# Raspberry.net
KiCad netlist of a schematic drawn in Altium Designer
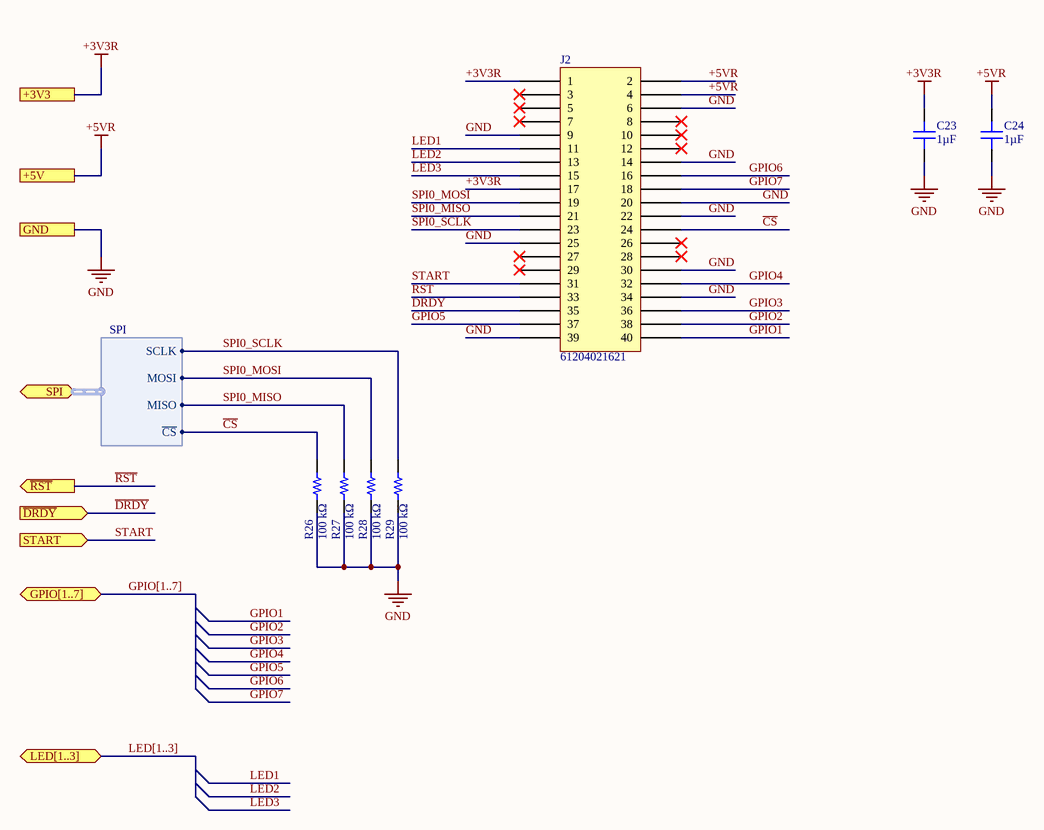
[diagram p0: Raspberry.SchDoc]

(export (version "E")
  (design (tool "Eeschema 10.0.6"))
  (components
    (comp (ref "C23")
      (value "1µF")
      (footprint "CAP 0402_1005")
      (description "CAP CER 1UF 16V X5R 0402")
      (fields (field (name "PART NUMBER") "0402BW105K160NGT") (field (name "MANUFACTURER") "Knowles Novacap"))
      (libsource (lib "Generic Altium Database") (part "Capacitor"))
    )
    (comp (ref "C24")
      (value "1µF")
      (footprint "CAP 0402_1005")
      (description "CAP CER 1UF 16V X5R 0402")
      (fields (field (name "PART NUMBER") "0402BW105K160NGT") (field (name "MANUFACTURER") "Knowles Novacap"))
      (libsource (lib "Generic Altium Database") (part "Capacitor"))
    )
    (comp (ref "J2")
      (value "61204021621")
      (footprint "WURTH 61204021621")
      (description "CONN HEADER VERT 40POS 2.54MM")
      (fields (field (name "MANUFACTURER") "Würth Elektronik"))
      (libsource (lib "Generic Altium Database") (part "2X20 PIN"))
    )
    (comp (ref "R26")
      (value "100 kΩ")
      (footprint "RES 0402_1005")
      (description "RES SMD 100K OHM 1% 1/16W 0402")
      (fields (field (name "PART NUMBER") "AC0402FR-07100KL") (field (name "MANUFACTURER") "Yageo"))
      (libsource (lib "Generic Altium Database") (part "Resistor"))
    )
    (comp (ref "R27")
      (value "100 kΩ")
      (footprint "RES 0402_1005")
      (description "RES SMD 100K OHM 1% 1/16W 0402")
      (fields (field (name "PART NUMBER") "AC0402FR-07100KL") (field (name "MANUFACTURER") "Yageo"))
      (libsource (lib "Generic Altium Database") (part "Resistor"))
    )
    (comp (ref "R28")
      (value "100 kΩ")
      (footprint "RES 0402_1005")
      (description "RES SMD 100K OHM 1% 1/16W 0402")
      (fields (field (name "PART NUMBER") "AC0402FR-07100KL") (field (name "MANUFACTURER") "Yageo"))
      (libsource (lib "Generic Altium Database") (part "Resistor"))
    )
    (comp (ref "R29")
      (value "100 kΩ")
      (footprint "RES 0402_1005")
      (description "RES SMD 100K OHM 1% 1/16W 0402")
      (fields (field (name "PART NUMBER") "AC0402FR-07100KL") (field (name "MANUFACTURER") "Yageo"))
      (libsource (lib "Generic Altium Database") (part "Resistor"))
    )
  )
  (nets
    (net (code "2") (name "+3V3R") (class "Default")
      (node (ref "C23") (pin "1") (pinfunction "1_1") (pintype "passive"))
      (node (ref "J2") (pin "1") (pinfunction "1_1") (pintype "passive"))
      (node (ref "J2") (pin "17") (pinfunction "17_17") (pintype "passive"))
    )
    (net (code "3") (name "+5VR") (class "Default")
      (node (ref "C24") (pin "1") (pinfunction "1_1") (pintype "passive"))
      (node (ref "J2") (pin "2") (pinfunction "2_2") (pintype "passive"))
      (node (ref "J2") (pin "4") (pinfunction "4_4") (pintype "passive"))
    )
    (net (code "4") (name "/GPIO1") (class "Default")
      (node (ref "J2") (pin "40") (pinfunction "40_40") (pintype "passive"))
    )
    (net (code "5") (name "/GPIO2") (class "Default")
      (node (ref "J2") (pin "38") (pinfunction "38_38") (pintype "passive"))
    )
    (net (code "6") (name "/GPIO3") (class "Default")
      (node (ref "J2") (pin "36") (pinfunction "36_36") (pintype "passive"))
    )
    (net (code "7") (name "/GPIO4") (class "Default")
      (node (ref "J2") (pin "32") (pinfunction "32_32") (pintype "passive"))
    )
    (net (code "8") (name "/GPIO5") (class "Default")
      (node (ref "J2") (pin "37") (pinfunction "37_37") (pintype "passive"))
    )
    (net (code "9") (name "/GPIO6") (class "Default")
      (node (ref "J2") (pin "16") (pinfunction "16_16") (pintype "passive"))
    )
    (net (code "10") (name "/GPIO7") (class "Default")
      (node (ref "J2") (pin "18") (pinfunction "18_18") (pintype "passive"))
    )
    (net (code "12") (name "/LED1") (class "Default")
      (node (ref "J2") (pin "11") (pinfunction "11_11") (pintype "passive"))
    )
    (net (code "13") (name "/LED2") (class "Default")
      (node (ref "J2") (pin "13") (pinfunction "13_13") (pintype "passive"))
    )
    (net (code "14") (name "/LED3") (class "Default")
      (node (ref "J2") (pin "15") (pinfunction "15_15") (pintype "passive"))
    )
    (net (code "16") (name "/SPI0_MISO") (class "Default")
      (node (ref "J2") (pin "21") (pinfunction "21_21") (pintype "passive"))
      (node (ref "R27") (pin "1") (pinfunction "1_1") (pintype "passive"))
    )
    (net (code "17") (name "/SPI0_MOSI") (class "Default")
      (node (ref "J2") (pin "19") (pinfunction "19_19") (pintype "passive"))
      (node (ref "R28") (pin "1") (pinfunction "1_1") (pintype "passive"))
    )
    (net (code "18") (name "/SPI0_SCLK") (class "Default")
      (node (ref "J2") (pin "23") (pinfunction "23_23") (pintype "passive"))
      (node (ref "R29") (pin "1") (pinfunction "1_1") (pintype "passive"))
    )
    (net (code "19") (name "/START") (class "Default")
      (node (ref "J2") (pin "31") (pinfunction "31_31") (pintype "passive"))
    )
    (net (code "21") (name "/~{CS}") (class "Default")
      (node (ref "J2") (pin "24") (pinfunction "24_24") (pintype "passive"))
      (node (ref "R26") (pin "1") (pinfunction "1_1") (pintype "passive"))
    )
    (net (code "22") (name "/~{DRDY}") (class "Default")
      (node (ref "J2") (pin "35") (pinfunction "35_35") (pintype "passive"))
    )
    (net (code "23") (name "/~{RST}") (class "Default")
      (node (ref "J2") (pin "33") (pinfunction "33_33") (pintype "passive"))
    )
    (net (code "24") (name "GND") (class "Default")
      (node (ref "C23") (pin "2") (pinfunction "2_2") (pintype "passive"))
      (node (ref "C24") (pin "2") (pinfunction "2_2") (pintype "passive"))
      (node (ref "J2") (pin "14") (pinfunction "14_14") (pintype "passive"))
      (node (ref "J2") (pin "20") (pinfunction "20_20") (pintype "passive"))
      (node (ref "J2") (pin "22") (pinfunction "22_22") (pintype "passive"))
      (node (ref "J2") (pin "25") (pinfunction "25_25") (pintype "passive"))
      (node (ref "J2") (pin "30") (pinfunction "30_30") (pintype "passive"))
      (node (ref "J2") (pin "34") (pinfunction "34_34") (pintype "passive"))
      (node (ref "J2") (pin "39") (pinfunction "39_39") (pintype "passive"))
      (node (ref "J2") (pin "6") (pinfunction "6_6") (pintype "passive"))
      (node (ref "J2") (pin "9") (pinfunction "9_9") (pintype "passive"))
      (node (ref "R26") (pin "2") (pinfunction "2_2") (pintype "passive"))
      (node (ref "R27") (pin "2") (pinfunction "2_2") (pintype "passive"))
      (node (ref "R28") (pin "2") (pinfunction "2_2") (pintype "passive"))
      (node (ref "R29") (pin "2") (pinfunction "2_2") (pintype "passive"))
    )
    (net (code "25") (name "unconnected-(J2-Pad3)") (class "Default")
      (node (ref "J2") (pin "3") (pinfunction "3_3") (pintype "passive+no_connect"))
    )
    (net (code "26") (name "unconnected-(J2-Pad5)") (class "Default")
      (node (ref "J2") (pin "5") (pinfunction "5_5") (pintype "passive+no_connect"))
    )
    (net (code "27") (name "unconnected-(J2-Pad7)") (class "Default")
      (node (ref "J2") (pin "7") (pinfunction "7_7") (pintype "passive+no_connect"))
    )
    (net (code "28") (name "unconnected-(J2-Pad8)") (class "Default")
      (node (ref "J2") (pin "8") (pinfunction "8_8") (pintype "passive+no_connect"))
    )
    (net (code "29") (name "unconnected-(J2-Pad10)") (class "Default")
      (node (ref "J2") (pin "10") (pinfunction "10_10") (pintype "passive+no_connect"))
    )
    (net (code "30") (name "unconnected-(J2-Pad12)") (class "Default")
      (node (ref "J2") (pin "12") (pinfunction "12_12") (pintype "passive+no_connect"))
    )
    (net (code "31") (name "unconnected-(J2-Pad26)") (class "Default")
      (node (ref "J2") (pin "26") (pinfunction "26_26") (pintype "passive+no_connect"))
    )
    (net (code "32") (name "unconnected-(J2-Pad27)") (class "Default")
      (node (ref "J2") (pin "27") (pinfunction "27_27") (pintype "passive+no_connect"))
    )
    (net (code "33") (name "unconnected-(J2-Pad28)") (class "Default")
      (node (ref "J2") (pin "28") (pinfunction "28_28") (pintype "passive+no_connect"))
    )
    (net (code "34") (name "unconnected-(J2-Pad29)") (class "Default")
      (node (ref "J2") (pin "29") (pinfunction "29_29") (pintype "passive+no_connect"))
    )
  )
)
